# Tarjeta_SD_Interfaz.net
KiCad netlist of a schematic drawn in Altium Designer
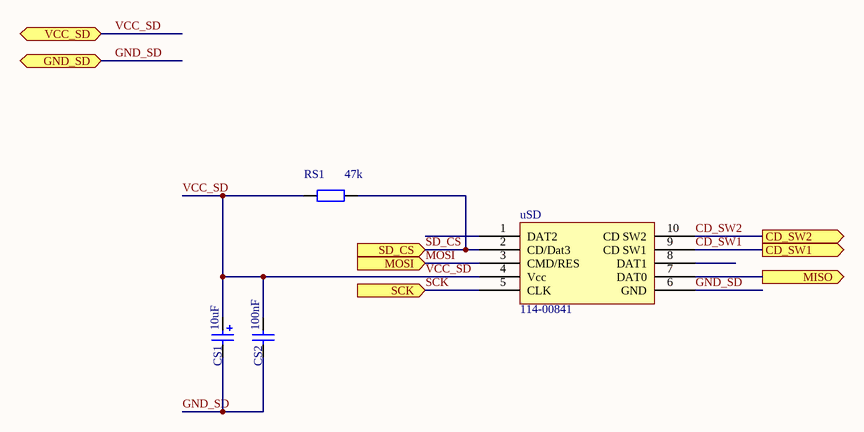
[diagram p0: Tarjeta_SD_Interfaz.SchDoc]

(export (version "E")
  (design (tool "Eeschema 10.0.6"))
  (components
    (comp (ref "CS1")
      (value "10uF")
      (footprint "6-0805_M")
      (description "Polarized Capacitor (SMD)")
      (fields (field (name "Comment") "Cap Pol3") (field (name "PUBLISHER") "Altium Limited"))
      (libsource (lib "Miscellaneous Devices") (part "Cap Pol3"))
    )
    (comp (ref "CS2")
      (value "100nF")
      (footprint "6-0805_M")
      (description "Capacitor (SMD)")
      (fields (field (name "Comment") "Cap") (field (name "PUBLISHER") "Altium Limited"))
      (libsource (lib "Miscellaneous Devices") (part "Cap Semi"))
    )
    (comp (ref "RS1")
      (value "47k")
      (footprint "6-0805_M")
      (description "Resistor(0805 - SMD)")
      (fields (field (name "Comment") "Res2") (field (name "PUBLISHER") "Altium Limited"))
      (libsource (lib "Miscellaneous Devices") (part "Res2"))
    )
    (comp (ref "uSD")
      (value "114-00841")
      (footprint "Amphenol 114-00841-68")
      (description "Micro SD None Push Connector Top Mount")
      (fields
        (field (name "MANUFACTURER") "Amphenol Shoumin Industry")
        (field (name "MAIL") "rouxfederico@hotmail.com")
      )
      (libsource (lib "SD_Card") (part "uSD Card Connector Amphenol 114-00841"))
    )
  )
  (nets
    (net (code "1") (name "/CD_SW1") (class "Default")
      (node (ref "uSD") (pin "9") (pinfunction "CD_SW1_9") (pintype "passive"))
    )
    (net (code "2") (name "/CD_SW2") (class "Default")
      (node (ref "uSD") (pin "10") (pinfunction "CD_SW2_10") (pintype "passive"))
    )
    (net (code "3") (name "/GND_SD") (class "Default")
      (node (ref "CS1") (pin "2") (pinfunction "2_2") (pintype "passive"))
      (node (ref "CS2") (pin "1") (pinfunction "1_1") (pintype "passive"))
      (node (ref "uSD") (pin "6") (pinfunction "GND_6") (pintype "power_in"))
    )
    (net (code "4") (name "/MISO") (class "Default")
      (node (ref "uSD") (pin "7") (pinfunction "DAT0_7") (pintype "passive"))
    )
    (net (code "5") (name "/MOSI") (class "Default")
      (node (ref "uSD") (pin "3") (pinfunction "CMD/RES_3") (pintype "passive"))
    )
    (net (code "6") (name "/SCK") (class "Default")
      (node (ref "uSD") (pin "5") (pinfunction "CLK_5") (pintype "passive"))
    )
    (net (code "7") (name "/SD_CS") (class "Default")
      (node (ref "RS1") (pin "2") (pinfunction "2_2") (pintype "passive"))
      (node (ref "uSD") (pin "2") (pinfunction "CD/Dat3_2") (pintype "passive"))
    )
    (net (code "8") (name "/VCC_SD") (class "Default")
      (node (ref "CS1") (pin "1") (pinfunction "1_1") (pintype "passive"))
      (node (ref "CS2") (pin "2") (pinfunction "2_2") (pintype "passive"))
      (node (ref "RS1") (pin "1") (pinfunction "1_1") (pintype "passive"))
      (node (ref "uSD") (pin "4") (pinfunction "Vcc_4") (pintype "power_in"))
    )
    (net (code "9") (name "unconnected-(uSD-DAT1-Pad8)") (class "Default")
      (node (ref "uSD") (pin "8") (pinfunction "DAT1_8") (pintype "passive"))
    )
    (net (code "10") (name "unconnected-(uSD-DAT2-Pad1)") (class "Default")
      (node (ref "uSD") (pin "1") (pinfunction "DAT2_1") (pintype "passive"))
    )
  )
)
